# MQBoard.net
KiCad netlist of a schematic drawn in EAGLE
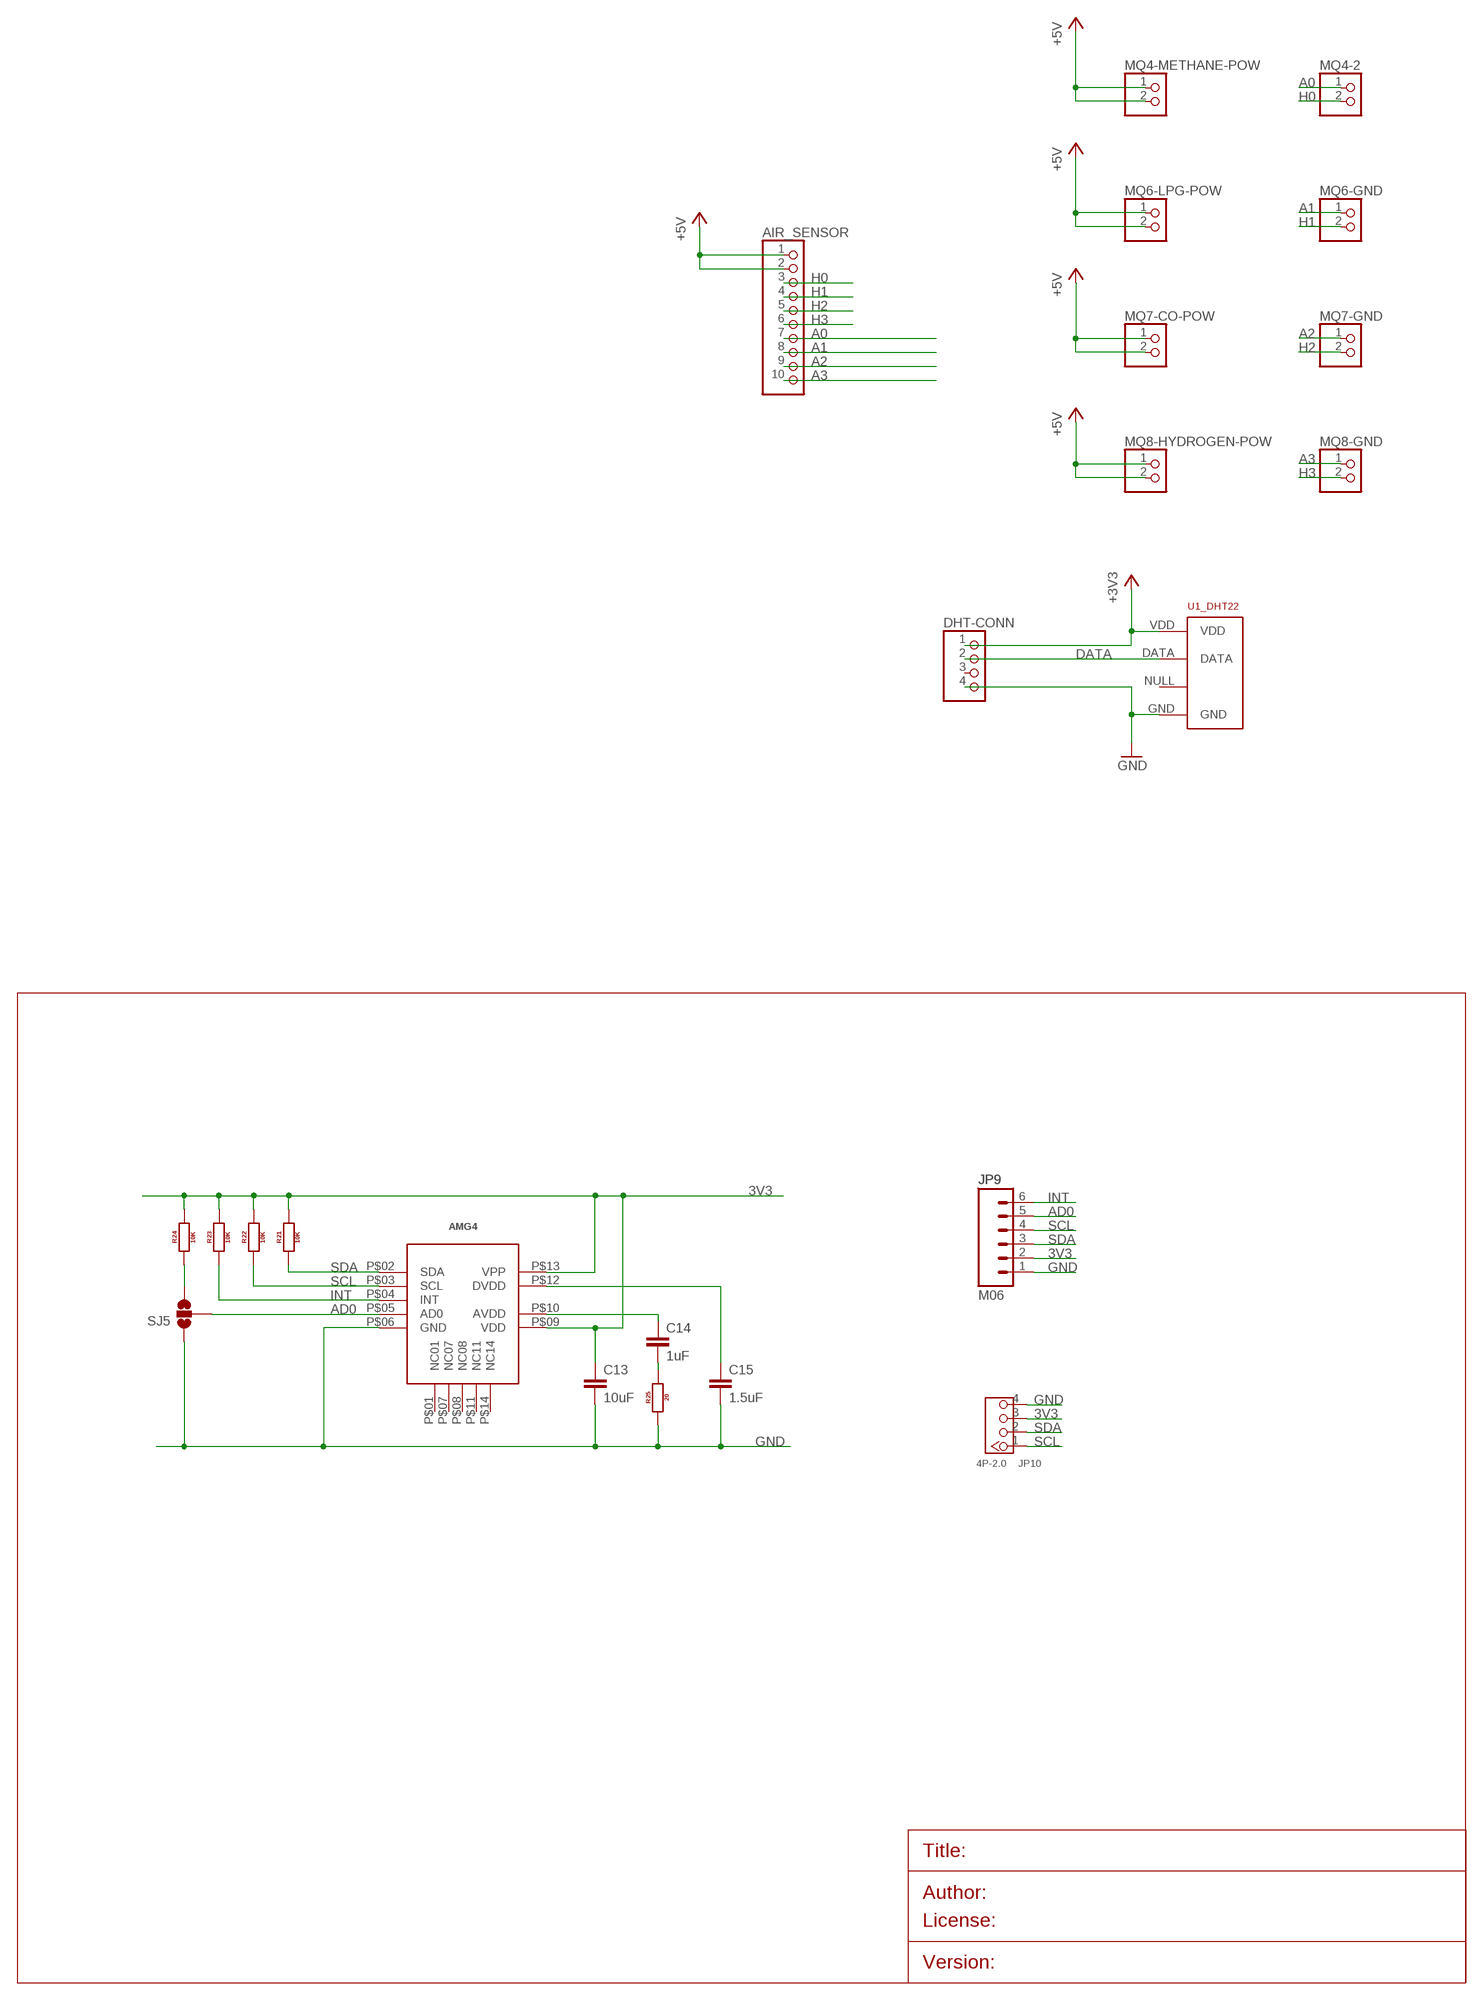
[diagram p0: schematic, sheet 1, part 1 of 2]
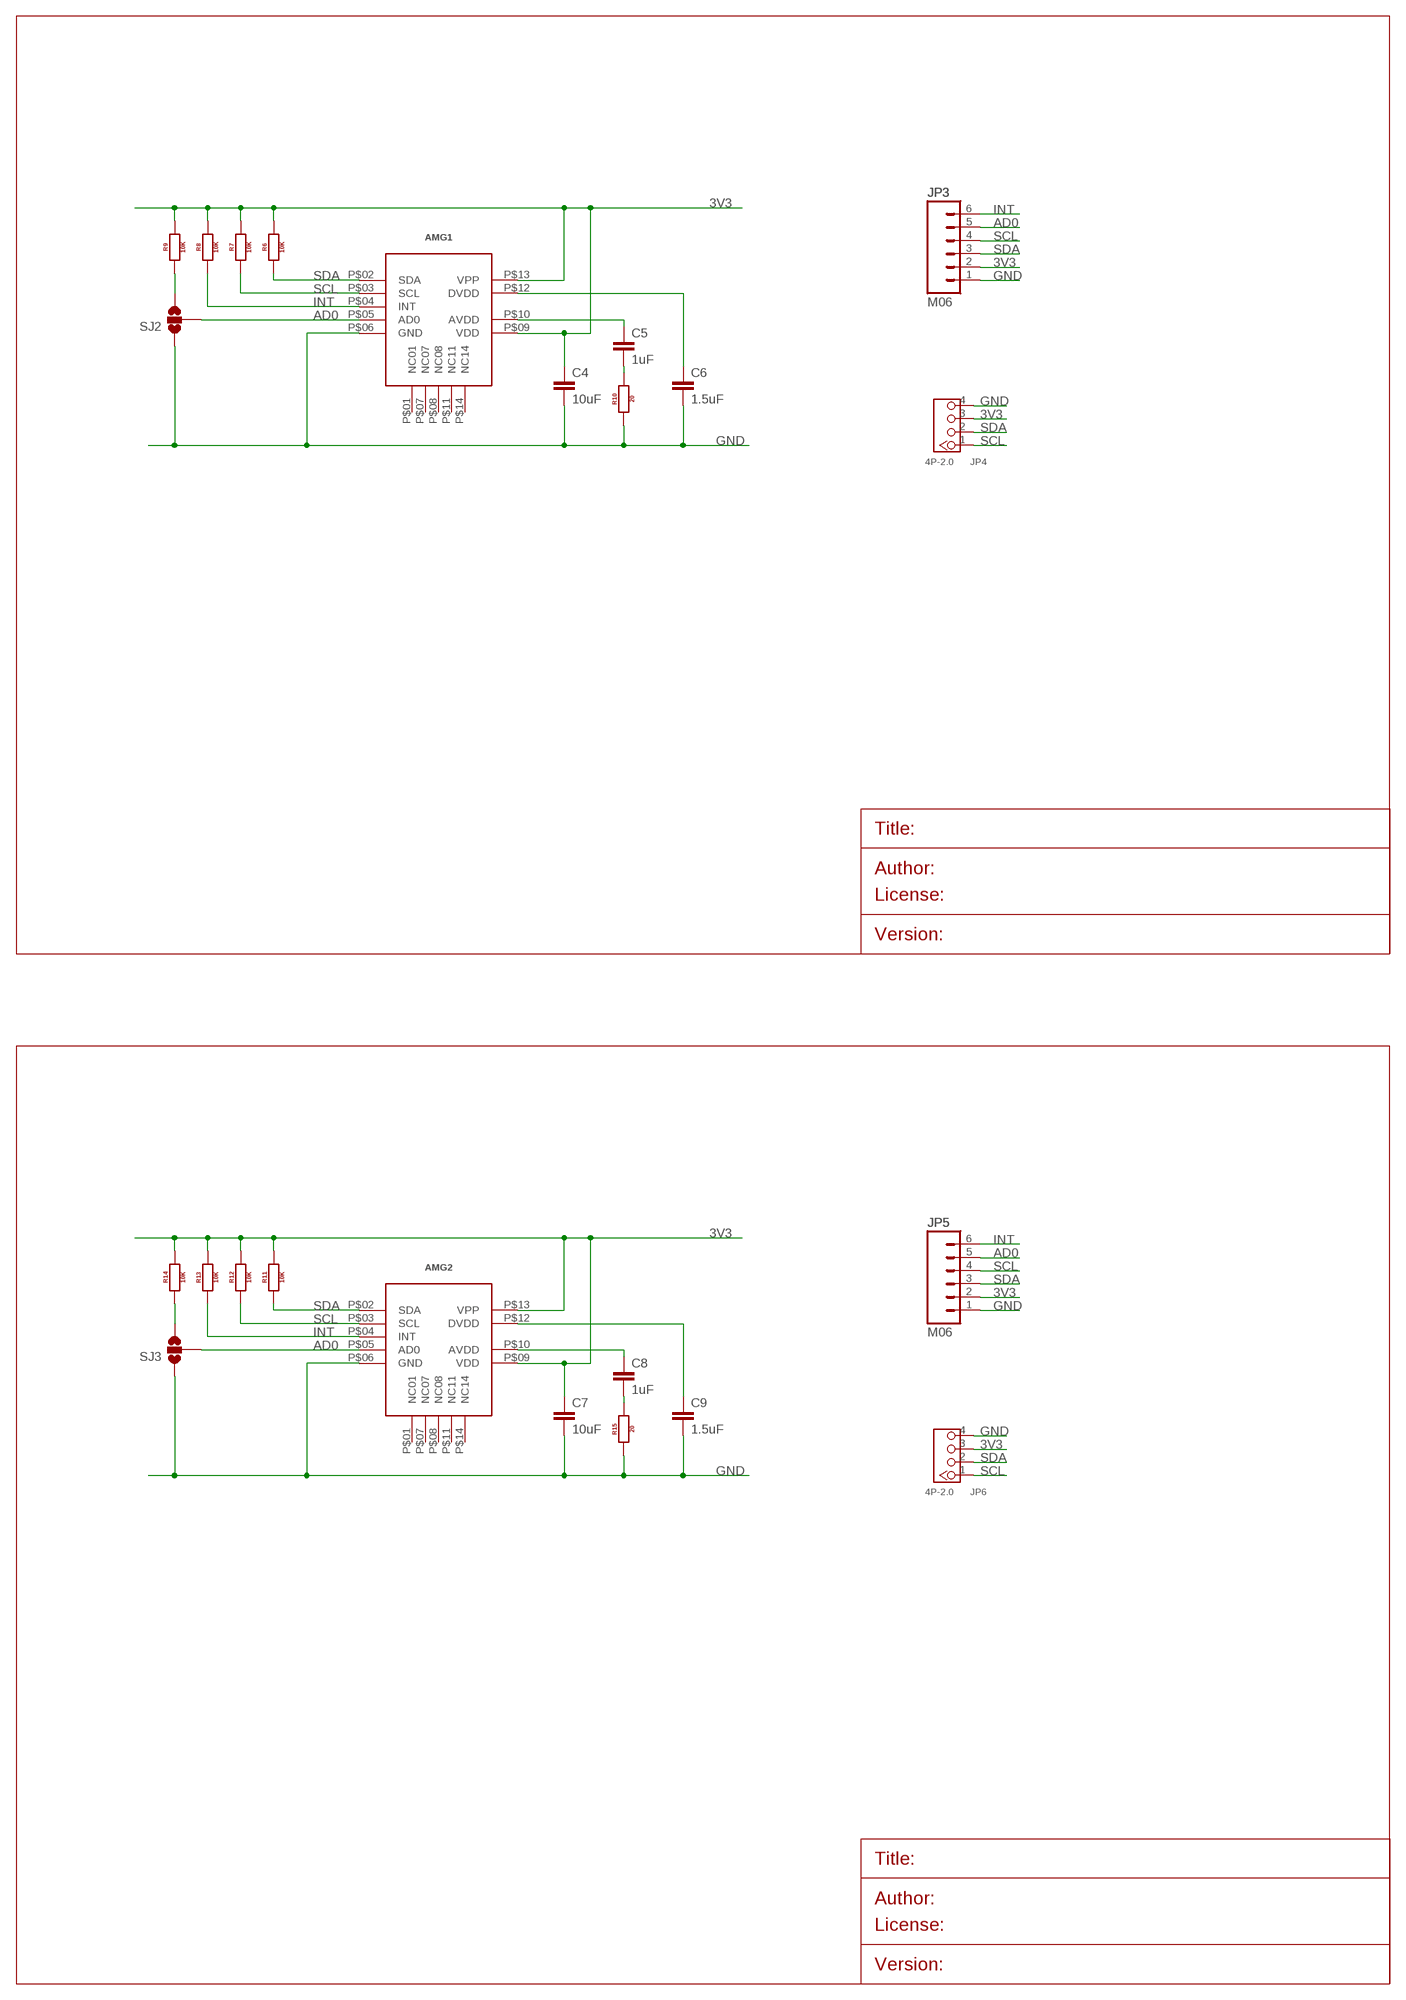
[diagram p1: schematic, sheet 1, part 2 of 2]

(export (version "E")
  (design (tool "Eeschema 10.0.6"))
  (components
    (comp (ref "AIR_SENSOR")
      (value "PINHD-1X10")
      (footprint "eagle-import:1X10")
      (libsource (lib "eagle-import") (part "PINHD-1X10"))
    )
    (comp (ref "AMG1")
      (value "AMG88XX")
      (footprint "eagle-import:AMG88XX")
      (libsource (lib "eagle-import") (part "AMG88XX"))
    )
    (comp (ref "AMG2")
      (value "AMG88XX")
      (footprint "eagle-import:AMG88XX")
      (libsource (lib "eagle-import") (part "AMG88XX"))
    )
    (comp (ref "AMG4")
      (value "AMG88XX")
      (footprint "eagle-import:AMG88XX")
      (libsource (lib "eagle-import") (part "AMG88XX"))
    )
    (comp (ref "C4")
      (value "10uF")
      (footprint "eagle-import:0805")
      (libsource (lib "eagle-import") (part "C-EU0805"))
    )
    (comp (ref "C5")
      (value "1uF")
      (footprint "eagle-import:0805")
      (libsource (lib "eagle-import") (part "C-EU0805"))
    )
    (comp (ref "C6")
      (value "1.5uF")
      (footprint "eagle-import:0805")
      (libsource (lib "eagle-import") (part "C-EU0805"))
    )
    (comp (ref "C7")
      (value "10uF")
      (footprint "eagle-import:0805")
      (libsource (lib "eagle-import") (part "C-EU0805"))
    )
    (comp (ref "C8")
      (value "1uF")
      (footprint "eagle-import:0805")
      (libsource (lib "eagle-import") (part "C-EU0805"))
    )
    (comp (ref "C9")
      (value "1.5uF")
      (footprint "eagle-import:0805")
      (libsource (lib "eagle-import") (part "C-EU0805"))
    )
    (comp (ref "C13")
      (value "10uF")
      (footprint "eagle-import:0805")
      (libsource (lib "eagle-import") (part "C-EU0805"))
    )
    (comp (ref "C14")
      (value "1uF")
      (footprint "eagle-import:0805")
      (libsource (lib "eagle-import") (part "C-EU0805"))
    )
    (comp (ref "C15")
      (value "1.5uF")
      (footprint "eagle-import:0805")
      (libsource (lib "eagle-import") (part "C-EU0805"))
    )
    (comp (ref "DHT-CONN")
      (value "PINHD-1X4")
      (footprint "eagle-import:1X04")
      (libsource (lib "eagle-import") (part "PINHD-1X4"))
    )
    (comp (ref "JP3")
      (value "M06")
      (footprint "eagle-import:1X06_NO_SILK")
      (libsource (lib "eagle-import") (part "M06"))
    )
    (comp (ref "JP4")
      (value "4P-2.0")
      (footprint "eagle-import:HW4-2.0")
      (libsource (lib "eagle-import") (part "GROVE-CONNECTOR-DIP(4P-2.0)"))
    )
    (comp (ref "JP5")
      (value "M06")
      (footprint "eagle-import:1X06_NO_SILK")
      (libsource (lib "eagle-import") (part "M06"))
    )
    (comp (ref "JP6")
      (value "4P-2.0")
      (footprint "eagle-import:HW4-2.0")
      (libsource (lib "eagle-import") (part "GROVE-CONNECTOR-DIP(4P-2.0)"))
    )
    (comp (ref "JP9")
      (value "M06")
      (footprint "eagle-import:1X06_NO_SILK")
      (libsource (lib "eagle-import") (part "M06"))
    )
    (comp (ref "JP10")
      (value "4P-2.0")
      (footprint "eagle-import:HW4-2.0")
      (libsource (lib "eagle-import") (part "GROVE-CONNECTOR-DIP(4P-2.0)"))
    )
    (comp (ref "MQ4-2")
      (value "PINHD-1X2")
      (footprint "eagle-import:1X02")
      (libsource (lib "eagle-import") (part "PINHD-1X2"))
    )
    (comp (ref "MQ4-METHANE-POW")
      (value "PINHD-1X2")
      (footprint "eagle-import:1X02")
      (libsource (lib "eagle-import") (part "PINHD-1X2"))
    )
    (comp (ref "MQ6-GND")
      (value "PINHD-1X2")
      (footprint "eagle-import:1X02")
      (libsource (lib "eagle-import") (part "PINHD-1X2"))
    )
    (comp (ref "MQ6-LPG-POW")
      (value "PINHD-1X2")
      (footprint "eagle-import:1X02")
      (libsource (lib "eagle-import") (part "PINHD-1X2"))
    )
    (comp (ref "MQ7-CO-POW")
      (value "PINHD-1X2")
      (footprint "eagle-import:1X02")
      (libsource (lib "eagle-import") (part "PINHD-1X2"))
    )
    (comp (ref "MQ7-GND")
      (value "PINHD-1X2")
      (footprint "eagle-import:1X02")
      (libsource (lib "eagle-import") (part "PINHD-1X2"))
    )
    (comp (ref "MQ8-GND")
      (value "PINHD-1X2")
      (footprint "eagle-import:1X02")
      (libsource (lib "eagle-import") (part "PINHD-1X2"))
    )
    (comp (ref "MQ8-HYDROGEN-POW")
      (value "PINHD-1X2")
      (footprint "eagle-import:1X02")
      (libsource (lib "eagle-import") (part "PINHD-1X2"))
    )
    (comp (ref "R6")
      (value "10K")
      (footprint "eagle-import:0805")
      (libsource (lib "eagle-import") (part "RESISTOR0805"))
    )
    (comp (ref "R7")
      (value "10K")
      (footprint "eagle-import:0805")
      (libsource (lib "eagle-import") (part "RESISTOR0805"))
    )
    (comp (ref "R8")
      (value "10K")
      (footprint "eagle-import:0805")
      (libsource (lib "eagle-import") (part "RESISTOR0805"))
    )
    (comp (ref "R9")
      (value "10K")
      (footprint "eagle-import:0805")
      (libsource (lib "eagle-import") (part "RESISTOR0805"))
    )
    (comp (ref "R10")
      (value "20")
      (footprint "eagle-import:0805")
      (libsource (lib "eagle-import") (part "RESISTOR0805"))
    )
    (comp (ref "R11")
      (value "10K")
      (footprint "eagle-import:0805")
      (libsource (lib "eagle-import") (part "RESISTOR0805"))
    )
    (comp (ref "R12")
      (value "10K")
      (footprint "eagle-import:0805")
      (libsource (lib "eagle-import") (part "RESISTOR0805"))
    )
    (comp (ref "R13")
      (value "10K")
      (footprint "eagle-import:0805")
      (libsource (lib "eagle-import") (part "RESISTOR0805"))
    )
    (comp (ref "R14")
      (value "10K")
      (footprint "eagle-import:0805")
      (libsource (lib "eagle-import") (part "RESISTOR0805"))
    )
    (comp (ref "R15")
      (value "20")
      (footprint "eagle-import:0805")
      (libsource (lib "eagle-import") (part "RESISTOR0805"))
    )
    (comp (ref "R21")
      (value "10K")
      (footprint "eagle-import:0805")
      (libsource (lib "eagle-import") (part "RESISTOR0805"))
    )
    (comp (ref "R22")
      (value "10K")
      (footprint "eagle-import:0805")
      (libsource (lib "eagle-import") (part "RESISTOR0805"))
    )
    (comp (ref "R23")
      (value "10K")
      (footprint "eagle-import:0805")
      (libsource (lib "eagle-import") (part "RESISTOR0805"))
    )
    (comp (ref "R24")
      (value "10K")
      (footprint "eagle-import:0805")
      (libsource (lib "eagle-import") (part "RESISTOR0805"))
    )
    (comp (ref "R25")
      (value "20")
      (footprint "eagle-import:0805")
      (libsource (lib "eagle-import") (part "RESISTOR0805"))
    )
    (comp (ref "SJ2")
      (value "SOLDERJUMPER_2WAYS")
      (footprint "eagle-import:SJ_3")
      (libsource (lib "eagle-import") (part "SOLDERJUMPER_2WAYS"))
    )
    (comp (ref "SJ3")
      (value "SOLDERJUMPER_2WAYS")
      (footprint "eagle-import:SJ_3")
      (libsource (lib "eagle-import") (part "SOLDERJUMPER_2WAYS"))
    )
    (comp (ref "SJ5")
      (value "SOLDERJUMPER_2WAYS")
      (footprint "eagle-import:SJ_3")
      (libsource (lib "eagle-import") (part "SOLDERJUMPER_2WAYS"))
    )
    (comp (ref "U1_DHT22")
      (value "RHT03_DHT-22_AM2302")
      (footprint "eagle-import:RHT03_DHT-22")
      (libsource (lib "eagle-import") (part "RHT03_DHT-22_AM2302"))
    )
  )
  (nets
    (net (code "1") (name "+3V3") (class "Default")
      (node (ref "DHT-CONN") (pin "1") (pinfunction "1_1") (pintype "passive"))
      (node (ref "U1_DHT22") (pin "VDD") (pinfunction "VDD_VDD") (pintype "power_in"))
    )
    (net (code "2") (name "+5V") (class "Default")
      (node (ref "AIR_SENSOR") (pin "1") (pinfunction "1_1") (pintype "passive"))
      (node (ref "AIR_SENSOR") (pin "2") (pinfunction "2_2") (pintype "passive"))
      (node (ref "MQ4-METHANE-POW") (pin "1") (pinfunction "1_1") (pintype "passive"))
      (node (ref "MQ4-METHANE-POW") (pin "2") (pinfunction "2_2") (pintype "passive"))
      (node (ref "MQ6-LPG-POW") (pin "1") (pinfunction "1_1") (pintype "passive"))
      (node (ref "MQ6-LPG-POW") (pin "2") (pinfunction "2_2") (pintype "passive"))
      (node (ref "MQ7-CO-POW") (pin "1") (pinfunction "1_1") (pintype "passive"))
      (node (ref "MQ7-CO-POW") (pin "2") (pinfunction "2_2") (pintype "passive"))
      (node (ref "MQ8-HYDROGEN-POW") (pin "1") (pinfunction "1_1") (pintype "passive"))
      (node (ref "MQ8-HYDROGEN-POW") (pin "2") (pinfunction "2_2") (pintype "passive"))
    )
    (net (code "3") (name "/3V3") (class "Default")
      (node (ref "AMG1") (pin "P$09") (pinfunction "VDD_P$09") (pintype "power_in"))
      (node (ref "AMG1") (pin "P$13") (pinfunction "VPP_P$13") (pintype "power_in"))
      (node (ref "AMG2") (pin "P$09") (pinfunction "VDD_P$09") (pintype "power_in"))
      (node (ref "AMG2") (pin "P$13") (pinfunction "VPP_P$13") (pintype "power_in"))
      (node (ref "AMG4") (pin "P$09") (pinfunction "VDD_P$09") (pintype "power_in"))
      (node (ref "AMG4") (pin "P$13") (pinfunction "VPP_P$13") (pintype "power_in"))
      (node (ref "C13") (pin "1") (pinfunction "1_1") (pintype "passive"))
      (node (ref "C4") (pin "1") (pinfunction "1_1") (pintype "passive"))
      (node (ref "C7") (pin "1") (pinfunction "1_1") (pintype "passive"))
      (node (ref "JP10") (pin "3") (pinfunction "3_3") (pintype "bidirectional"))
      (node (ref "JP3") (pin "2") (pinfunction "2_2") (pintype "passive"))
      (node (ref "JP4") (pin "3") (pinfunction "3_3") (pintype "bidirectional"))
      (node (ref "JP5") (pin "2") (pinfunction "2_2") (pintype "passive"))
      (node (ref "JP6") (pin "3") (pinfunction "3_3") (pintype "bidirectional"))
      (node (ref "JP9") (pin "2") (pinfunction "2_2") (pintype "passive"))
      (node (ref "R11") (pin "2") (pinfunction "2_2") (pintype "passive"))
      (node (ref "R12") (pin "2") (pinfunction "2_2") (pintype "passive"))
      (node (ref "R13") (pin "2") (pinfunction "2_2") (pintype "passive"))
      (node (ref "R14") (pin "2") (pinfunction "2_2") (pintype "passive"))
      (node (ref "R21") (pin "2") (pinfunction "2_2") (pintype "passive"))
      (node (ref "R22") (pin "2") (pinfunction "2_2") (pintype "passive"))
      (node (ref "R23") (pin "2") (pinfunction "2_2") (pintype "passive"))
      (node (ref "R24") (pin "2") (pinfunction "2_2") (pintype "passive"))
      (node (ref "R6") (pin "2") (pinfunction "2_2") (pintype "passive"))
      (node (ref "R7") (pin "2") (pinfunction "2_2") (pintype "passive"))
      (node (ref "R8") (pin "2") (pinfunction "2_2") (pintype "passive"))
      (node (ref "R9") (pin "2") (pinfunction "2_2") (pintype "passive"))
    )
    (net (code "4") (name "/A0") (class "Default")
      (node (ref "AIR_SENSOR") (pin "7") (pinfunction "7_7") (pintype "passive"))
      (node (ref "MQ4-2") (pin "1") (pinfunction "1_1") (pintype "passive"))
    )
    (net (code "5") (name "/A1") (class "Default")
      (node (ref "AIR_SENSOR") (pin "8") (pinfunction "8_8") (pintype "passive"))
      (node (ref "MQ6-GND") (pin "1") (pinfunction "1_1") (pintype "passive"))
    )
    (net (code "6") (name "/A2") (class "Default")
      (node (ref "AIR_SENSOR") (pin "9") (pinfunction "9_9") (pintype "passive"))
      (node (ref "MQ7-GND") (pin "1") (pinfunction "1_1") (pintype "passive"))
    )
    (net (code "7") (name "/A3") (class "Default")
      (node (ref "AIR_SENSOR") (pin "10") (pinfunction "10_10") (pintype "passive"))
      (node (ref "MQ8-GND") (pin "1") (pinfunction "1_1") (pintype "passive"))
    )
    (net (code "8") (name "/AD0") (class "Default")
      (node (ref "AMG1") (pin "P$05") (pinfunction "AD0_P$05") (pintype "bidirectional"))
      (node (ref "AMG2") (pin "P$05") (pinfunction "AD0_P$05") (pintype "bidirectional"))
      (node (ref "AMG4") (pin "P$05") (pinfunction "AD0_P$05") (pintype "bidirectional"))
      (node (ref "JP3") (pin "5") (pinfunction "5_5") (pintype "passive"))
      (node (ref "JP5") (pin "5") (pinfunction "5_5") (pintype "passive"))
      (node (ref "JP9") (pin "5") (pinfunction "5_5") (pintype "passive"))
      (node (ref "SJ2") (pin "2") (pinfunction "2_2") (pintype "passive"))
      (node (ref "SJ3") (pin "2") (pinfunction "2_2") (pintype "passive"))
      (node (ref "SJ5") (pin "2") (pinfunction "2_2") (pintype "passive"))
    )
    (net (code "9") (name "/DATA") (class "Default")
      (node (ref "DHT-CONN") (pin "2") (pinfunction "2_2") (pintype "passive"))
      (node (ref "U1_DHT22") (pin "DATA") (pinfunction "DATA_DATA") (pintype "bidirectional"))
    )
    (net (code "10") (name "/H0") (class "Default")
      (node (ref "AIR_SENSOR") (pin "3") (pinfunction "3_3") (pintype "passive"))
      (node (ref "MQ4-2") (pin "2") (pinfunction "2_2") (pintype "passive"))
    )
    (net (code "11") (name "/H1") (class "Default")
      (node (ref "AIR_SENSOR") (pin "4") (pinfunction "4_4") (pintype "passive"))
      (node (ref "MQ6-GND") (pin "2") (pinfunction "2_2") (pintype "passive"))
    )
    (net (code "12") (name "/H2") (class "Default")
      (node (ref "AIR_SENSOR") (pin "5") (pinfunction "5_5") (pintype "passive"))
      (node (ref "MQ7-GND") (pin "2") (pinfunction "2_2") (pintype "passive"))
    )
    (net (code "13") (name "/H3") (class "Default")
      (node (ref "AIR_SENSOR") (pin "6") (pinfunction "6_6") (pintype "passive"))
      (node (ref "MQ8-GND") (pin "2") (pinfunction "2_2") (pintype "passive"))
    )
    (net (code "14") (name "/INT") (class "Default")
      (node (ref "AMG1") (pin "P$04") (pinfunction "INT_P$04") (pintype "bidirectional"))
      (node (ref "AMG2") (pin "P$04") (pinfunction "INT_P$04") (pintype "bidirectional"))
      (node (ref "AMG4") (pin "P$04") (pinfunction "INT_P$04") (pintype "bidirectional"))
      (node (ref "JP3") (pin "6") (pinfunction "6_6") (pintype "passive"))
      (node (ref "JP5") (pin "6") (pinfunction "6_6") (pintype "passive"))
      (node (ref "JP9") (pin "6") (pinfunction "6_6") (pintype "passive"))
      (node (ref "R13") (pin "1") (pinfunction "1_1") (pintype "passive"))
      (node (ref "R23") (pin "1") (pinfunction "1_1") (pintype "passive"))
      (node (ref "R8") (pin "1") (pinfunction "1_1") (pintype "passive"))
    )
    (net (code "15") (name "/SCL") (class "Default")
      (node (ref "AMG1") (pin "P$03") (pinfunction "SCL_P$03") (pintype "bidirectional"))
      (node (ref "AMG2") (pin "P$03") (pinfunction "SCL_P$03") (pintype "bidirectional"))
      (node (ref "AMG4") (pin "P$03") (pinfunction "SCL_P$03") (pintype "bidirectional"))
      (node (ref "JP10") (pin "1") (pinfunction "1_1") (pintype "bidirectional"))
      (node (ref "JP3") (pin "4") (pinfunction "4_4") (pintype "passive"))
      (node (ref "JP4") (pin "1") (pinfunction "1_1") (pintype "bidirectional"))
      (node (ref "JP5") (pin "4") (pinfunction "4_4") (pintype "passive"))
      (node (ref "JP6") (pin "1") (pinfunction "1_1") (pintype "bidirectional"))
      (node (ref "JP9") (pin "4") (pinfunction "4_4") (pintype "passive"))
      (node (ref "R12") (pin "1") (pinfunction "1_1") (pintype "passive"))
      (node (ref "R22") (pin "1") (pinfunction "1_1") (pintype "passive"))
      (node (ref "R7") (pin "1") (pinfunction "1_1") (pintype "passive"))
    )
    (net (code "16") (name "/SDA") (class "Default")
      (node (ref "AMG1") (pin "P$02") (pinfunction "SDA_P$02") (pintype "bidirectional"))
      (node (ref "AMG2") (pin "P$02") (pinfunction "SDA_P$02") (pintype "bidirectional"))
      (node (ref "AMG4") (pin "P$02") (pinfunction "SDA_P$02") (pintype "bidirectional"))
      (node (ref "JP10") (pin "2") (pinfunction "2_2") (pintype "bidirectional"))
      (node (ref "JP3") (pin "3") (pinfunction "3_3") (pintype "passive"))
      (node (ref "JP4") (pin "2") (pinfunction "2_2") (pintype "bidirectional"))
      (node (ref "JP5") (pin "3") (pinfunction "3_3") (pintype "passive"))
      (node (ref "JP6") (pin "2") (pinfunction "2_2") (pintype "bidirectional"))
      (node (ref "JP9") (pin "3") (pinfunction "3_3") (pintype "passive"))
      (node (ref "R11") (pin "1") (pinfunction "1_1") (pintype "passive"))
      (node (ref "R21") (pin "1") (pinfunction "1_1") (pintype "passive"))
      (node (ref "R6") (pin "1") (pinfunction "1_1") (pintype "passive"))
    )
    (net (code "17") (name "GND") (class "Default")
      (node (ref "AMG1") (pin "P$06") (pinfunction "GND_P$06") (pintype "power_in"))
      (node (ref "AMG2") (pin "P$06") (pinfunction "GND_P$06") (pintype "power_in"))
      (node (ref "AMG4") (pin "P$06") (pinfunction "GND_P$06") (pintype "power_in"))
      (node (ref "C13") (pin "2") (pinfunction "2_2") (pintype "passive"))
      (node (ref "C15") (pin "2") (pinfunction "2_2") (pintype "passive"))
      (node (ref "C4") (pin "2") (pinfunction "2_2") (pintype "passive"))
      (node (ref "C6") (pin "2") (pinfunction "2_2") (pintype "passive"))
      (node (ref "C7") (pin "2") (pinfunction "2_2") (pintype "passive"))
      (node (ref "C9") (pin "2") (pinfunction "2_2") (pintype "passive"))
      (node (ref "DHT-CONN") (pin "4") (pinfunction "4_4") (pintype "passive"))
      (node (ref "JP10") (pin "4") (pinfunction "4_4") (pintype "bidirectional"))
      (node (ref "JP3") (pin "1") (pinfunction "1_1") (pintype "passive"))
      (node (ref "JP4") (pin "4") (pinfunction "4_4") (pintype "bidirectional"))
      (node (ref "JP5") (pin "1") (pinfunction "1_1") (pintype "passive"))
      (node (ref "JP6") (pin "4") (pinfunction "4_4") (pintype "bidirectional"))
      (node (ref "JP9") (pin "1") (pinfunction "1_1") (pintype "passive"))
      (node (ref "R10") (pin "1") (pinfunction "1_1") (pintype "passive"))
      (node (ref "R15") (pin "1") (pinfunction "1_1") (pintype "passive"))
      (node (ref "R25") (pin "1") (pinfunction "1_1") (pintype "passive"))
      (node (ref "SJ2") (pin "1") (pinfunction "1_1") (pintype "passive"))
      (node (ref "SJ3") (pin "1") (pinfunction "1_1") (pintype "passive"))
      (node (ref "SJ5") (pin "1") (pinfunction "1_1") (pintype "passive"))
      (node (ref "U1_DHT22") (pin "GND") (pinfunction "GND_GND") (pintype "power_in"))
    )
    (net (code "18") (name "Net-(AMG1-AVDD)") (class "Default")
      (node (ref "AMG1") (pin "P$10") (pinfunction "AVDD_P$10") (pintype "bidirectional"))
      (node (ref "C5") (pin "1") (pinfunction "1_1") (pintype "passive"))
    )
    (net (code "19") (name "Net-(AMG1-DVDD)") (class "Default")
      (node (ref "AMG1") (pin "P$12") (pinfunction "DVDD_P$12") (pintype "bidirectional"))
      (node (ref "C6") (pin "1") (pinfunction "1_1") (pintype "passive"))
    )
    (net (code "20") (name "Net-(AMG2-AVDD)") (class "Default")
      (node (ref "AMG2") (pin "P$10") (pinfunction "AVDD_P$10") (pintype "bidirectional"))
      (node (ref "C8") (pin "1") (pinfunction "1_1") (pintype "passive"))
    )
    (net (code "21") (name "Net-(AMG2-DVDD)") (class "Default")
      (node (ref "AMG2") (pin "P$12") (pinfunction "DVDD_P$12") (pintype "bidirectional"))
      (node (ref "C9") (pin "1") (pinfunction "1_1") (pintype "passive"))
    )
    (net (code "22") (name "Net-(AMG4-AVDD)") (class "Default")
      (node (ref "AMG4") (pin "P$10") (pinfunction "AVDD_P$10") (pintype "bidirectional"))
      (node (ref "C14") (pin "1") (pinfunction "1_1") (pintype "passive"))
    )
    (net (code "23") (name "Net-(AMG4-DVDD)") (class "Default")
      (node (ref "AMG4") (pin "P$12") (pinfunction "DVDD_P$12") (pintype "bidirectional"))
      (node (ref "C15") (pin "1") (pinfunction "1_1") (pintype "passive"))
    )
    (net (code "24") (name "Net-(C5-Pad2)") (class "Default")
      (node (ref "C5") (pin "2") (pinfunction "2_2") (pintype "passive"))
      (node (ref "R10") (pin "2") (pinfunction "2_2") (pintype "passive"))
    )
    (net (code "25") (name "Net-(C8-Pad2)") (class "Default")
      (node (ref "C8") (pin "2") (pinfunction "2_2") (pintype "passive"))
      (node (ref "R15") (pin "2") (pinfunction "2_2") (pintype "passive"))
    )
    (net (code "26") (name "Net-(C14-Pad2)") (class "Default")
      (node (ref "C14") (pin "2") (pinfunction "2_2") (pintype "passive"))
      (node (ref "R25") (pin "2") (pinfunction "2_2") (pintype "passive"))
    )
    (net (code "27") (name "Net-(R9-Pad1)") (class "Default")
      (node (ref "R9") (pin "1") (pinfunction "1_1") (pintype "passive"))
      (node (ref "SJ2") (pin "3") (pinfunction "3_3") (pintype "passive"))
    )
    (net (code "28") (name "Net-(R14-Pad1)") (class "Default")
      (node (ref "R14") (pin "1") (pinfunction "1_1") (pintype "passive"))
      (node (ref "SJ3") (pin "3") (pinfunction "3_3") (pintype "passive"))
    )
    (net (code "29") (name "Net-(R24-Pad1)") (class "Default")
      (node (ref "R24") (pin "1") (pinfunction "1_1") (pintype "passive"))
      (node (ref "SJ5") (pin "3") (pinfunction "3_3") (pintype "passive"))
    )
    (net (code "30") (name "unconnected-(AMG1-NC01-PadP$01)") (class "Default")
      (node (ref "AMG1") (pin "P$01") (pinfunction "NC01_P$01") (pintype "bidirectional"))
    )
    (net (code "31") (name "unconnected-(AMG1-NC07-PadP$07)") (class "Default")
      (node (ref "AMG1") (pin "P$07") (pinfunction "NC07_P$07") (pintype "bidirectional"))
    )
    (net (code "32") (name "unconnected-(AMG1-NC08-PadP$08)") (class "Default")
      (node (ref "AMG1") (pin "P$08") (pinfunction "NC08_P$08") (pintype "bidirectional"))
    )
    (net (code "33") (name "unconnected-(AMG1-NC11-PadP$11)") (class "Default")
      (node (ref "AMG1") (pin "P$11") (pinfunction "NC11_P$11") (pintype "bidirectional"))
    )
    (net (code "34") (name "unconnected-(AMG1-NC14-PadP$14)") (class "Default")
      (node (ref "AMG1") (pin "P$14") (pinfunction "NC14_P$14") (pintype "bidirectional"))
    )
    (net (code "35") (name "unconnected-(AMG2-NC01-PadP$01)") (class "Default")
      (node (ref "AMG2") (pin "P$01") (pinfunction "NC01_P$01") (pintype "bidirectional"))
    )
    (net (code "36") (name "unconnected-(AMG2-NC07-PadP$07)") (class "Default")
      (node (ref "AMG2") (pin "P$07") (pinfunction "NC07_P$07") (pintype "bidirectional"))
    )
    (net (code "37") (name "unconnected-(AMG2-NC08-PadP$08)") (class "Default")
      (node (ref "AMG2") (pin "P$08") (pinfunction "NC08_P$08") (pintype "bidirectional"))
    )
    (net (code "38") (name "unconnected-(AMG2-NC11-PadP$11)") (class "Default")
      (node (ref "AMG2") (pin "P$11") (pinfunction "NC11_P$11") (pintype "bidirectional"))
    )
    (net (code "39") (name "unconnected-(AMG2-NC14-PadP$14)") (class "Default")
      (node (ref "AMG2") (pin "P$14") (pinfunction "NC14_P$14") (pintype "bidirectional"))
    )
    (net (code "40") (name "unconnected-(AMG4-NC01-PadP$01)") (class "Default")
      (node (ref "AMG4") (pin "P$01") (pinfunction "NC01_P$01") (pintype "bidirectional"))
    )
    (net (code "41") (name "unconnected-(AMG4-NC07-PadP$07)") (class "Default")
      (node (ref "AMG4") (pin "P$07") (pinfunction "NC07_P$07") (pintype "bidirectional"))
    )
    (net (code "42") (name "unconnected-(AMG4-NC08-PadP$08)") (class "Default")
      (node (ref "AMG4") (pin "P$08") (pinfunction "NC08_P$08") (pintype "bidirectional"))
    )
    (net (code "43") (name "unconnected-(AMG4-NC11-PadP$11)") (class "Default")
      (node (ref "AMG4") (pin "P$11") (pinfunction "NC11_P$11") (pintype "bidirectional"))
    )
    (net (code "44") (name "unconnected-(AMG4-NC14-PadP$14)") (class "Default")
      (node (ref "AMG4") (pin "P$14") (pinfunction "NC14_P$14") (pintype "bidirectional"))
    )
    (net (code "45") (name "unconnected-(DHT-CONN-Pad3)") (class "Default")
      (node (ref "DHT-CONN") (pin "3") (pinfunction "3_3") (pintype "passive"))
    )
    (net (code "46") (name "unconnected-(U1_DHT22-PadNULL)") (class "Default")
      (node (ref "U1_DHT22") (pin "NULL") (pinfunction "NULL_NULL") (pintype "no_connect"))
    )
  )
)
